# KeypadKeyboard.net
KiCad netlist of a schematic drawn in Altium Designer
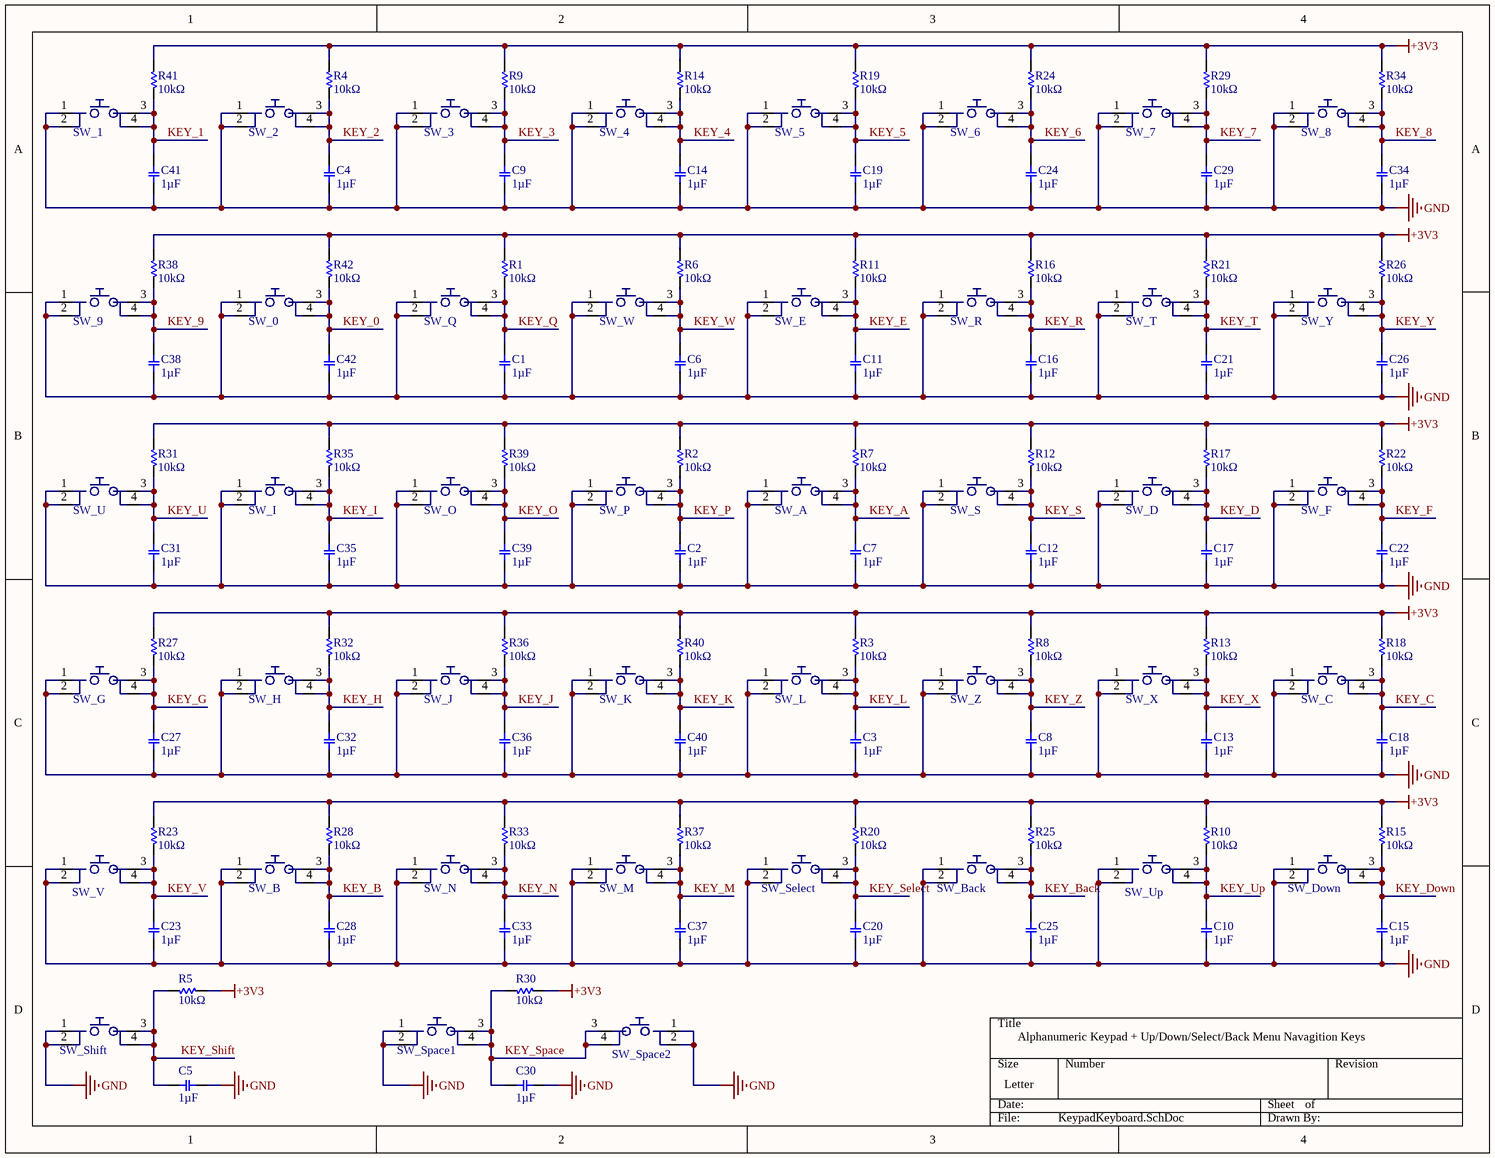
[diagram p0: KeypadKeyboard.SchDoc]

(export (version "E")
  (design (tool "Eeschema 10.0.6"))
  (components
    (comp (ref "C1")
      (value "1µF")
      (footprint "C0805(2012)_NP_med")
      (description "SMT Capacitor")
      (fields (field (name "TOLERANCE") "X7R"))
      (libsource (lib "ChipComponents") (part "CPN_SMT"))
    )
    (comp (ref "C2")
      (value "1µF")
      (footprint "C0805(2012)_NP_med")
      (description "SMT Capacitor")
      (fields (field (name "TOLERANCE") "X7R"))
      (libsource (lib "ChipComponents") (part "CPN_SMT"))
    )
    (comp (ref "C3")
      (value "1µF")
      (footprint "C0805(2012)_NP_med")
      (description "SMT Capacitor")
      (fields (field (name "TOLERANCE") "X7R"))
      (libsource (lib "ChipComponents") (part "CPN_SMT"))
    )
    (comp (ref "C4")
      (value "1µF")
      (footprint "C0805(2012)_NP_med")
      (description "SMT Capacitor")
      (fields (field (name "TOLERANCE") "X7R"))
      (libsource (lib "ChipComponents") (part "CPN_SMT"))
    )
    (comp (ref "C5")
      (value "1µF")
      (footprint "C0805(2012)_NP_med")
      (description "SMT Capacitor")
      (fields (field (name "TOLERANCE") "X7R"))
      (libsource (lib "ChipComponents") (part "CPN_SMT"))
    )
    (comp (ref "C6")
      (value "1µF")
      (footprint "C0805(2012)_NP_med")
      (description "SMT Capacitor")
      (fields (field (name "TOLERANCE") "X7R"))
      (libsource (lib "ChipComponents") (part "CPN_SMT"))
    )
    (comp (ref "C7")
      (value "1µF")
      (footprint "C0805(2012)_NP_med")
      (description "SMT Capacitor")
      (fields (field (name "TOLERANCE") "X7R"))
      (libsource (lib "ChipComponents") (part "CPN_SMT"))
    )
    (comp (ref "C8")
      (value "1µF")
      (footprint "C0805(2012)_NP_med")
      (description "SMT Capacitor")
      (fields (field (name "TOLERANCE") "X7R"))
      (libsource (lib "ChipComponents") (part "CPN_SMT"))
    )
    (comp (ref "C9")
      (value "1µF")
      (footprint "C0805(2012)_NP_med")
      (description "SMT Capacitor")
      (fields (field (name "TOLERANCE") "X7R"))
      (libsource (lib "ChipComponents") (part "CPN_SMT"))
    )
    (comp (ref "C10")
      (value "1µF")
      (footprint "C0805(2012)_NP_med")
      (description "SMT Capacitor")
      (fields (field (name "TOLERANCE") "X7R"))
      (libsource (lib "ChipComponents") (part "CPN_SMT"))
    )
    (comp (ref "C11")
      (value "1µF")
      (footprint "C0805(2012)_NP_med")
      (description "SMT Capacitor")
      (fields (field (name "TOLERANCE") "X7R"))
      (libsource (lib "ChipComponents") (part "CPN_SMT"))
    )
    (comp (ref "C12")
      (value "1µF")
      (footprint "C0805(2012)_NP_med")
      (description "SMT Capacitor")
      (fields (field (name "TOLERANCE") "X7R"))
      (libsource (lib "ChipComponents") (part "CPN_SMT"))
    )
    (comp (ref "C13")
      (value "1µF")
      (footprint "C0805(2012)_NP_med")
      (description "SMT Capacitor")
      (fields (field (name "TOLERANCE") "X7R"))
      (libsource (lib "ChipComponents") (part "CPN_SMT"))
    )
    (comp (ref "C14")
      (value "1µF")
      (footprint "C0805(2012)_NP_med")
      (description "SMT Capacitor")
      (fields (field (name "TOLERANCE") "X7R"))
      (libsource (lib "ChipComponents") (part "CPN_SMT"))
    )
    (comp (ref "C15")
      (value "1µF")
      (footprint "C0805(2012)_NP_med")
      (description "SMT Capacitor")
      (fields (field (name "TOLERANCE") "X7R"))
      (libsource (lib "ChipComponents") (part "CPN_SMT"))
    )
    (comp (ref "C16")
      (value "1µF")
      (footprint "C0805(2012)_NP_med")
      (description "SMT Capacitor")
      (fields (field (name "TOLERANCE") "X7R"))
      (libsource (lib "ChipComponents") (part "CPN_SMT"))
    )
    (comp (ref "C17")
      (value "1µF")
      (footprint "C0805(2012)_NP_med")
      (description "SMT Capacitor")
      (fields (field (name "TOLERANCE") "X7R"))
      (libsource (lib "ChipComponents") (part "CPN_SMT"))
    )
    (comp (ref "C18")
      (value "1µF")
      (footprint "C0805(2012)_NP_med")
      (description "SMT Capacitor")
      (fields (field (name "TOLERANCE") "X7R"))
      (libsource (lib "ChipComponents") (part "CPN_SMT"))
    )
    (comp (ref "C19")
      (value "1µF")
      (footprint "C0805(2012)_NP_med")
      (description "SMT Capacitor")
      (fields (field (name "TOLERANCE") "X7R"))
      (libsource (lib "ChipComponents") (part "CPN_SMT"))
    )
    (comp (ref "C20")
      (value "1µF")
      (footprint "C0805(2012)_NP_med")
      (description "SMT Capacitor")
      (fields (field (name "TOLERANCE") "X7R"))
      (libsource (lib "ChipComponents") (part "CPN_SMT"))
    )
    (comp (ref "C21")
      (value "1µF")
      (footprint "C0805(2012)_NP_med")
      (description "SMT Capacitor")
      (fields (field (name "TOLERANCE") "X7R"))
      (libsource (lib "ChipComponents") (part "CPN_SMT"))
    )
    (comp (ref "C22")
      (value "1µF")
      (footprint "C0805(2012)_NP_med")
      (description "SMT Capacitor")
      (fields (field (name "TOLERANCE") "X7R"))
      (libsource (lib "ChipComponents") (part "CPN_SMT"))
    )
    (comp (ref "C23")
      (value "1µF")
      (footprint "C0805(2012)_NP_med")
      (description "SMT Capacitor")
      (fields (field (name "TOLERANCE") "X7R"))
      (libsource (lib "ChipComponents") (part "CPN_SMT"))
    )
    (comp (ref "C24")
      (value "1µF")
      (footprint "C0805(2012)_NP_med")
      (description "SMT Capacitor")
      (fields (field (name "TOLERANCE") "X7R"))
      (libsource (lib "ChipComponents") (part "CPN_SMT"))
    )
    (comp (ref "C25")
      (value "1µF")
      (footprint "C0805(2012)_NP_med")
      (description "SMT Capacitor")
      (fields (field (name "TOLERANCE") "X7R"))
      (libsource (lib "ChipComponents") (part "CPN_SMT"))
    )
    (comp (ref "C26")
      (value "1µF")
      (footprint "C0805(2012)_NP_med")
      (description "SMT Capacitor")
      (fields (field (name "TOLERANCE") "X7R"))
      (libsource (lib "ChipComponents") (part "CPN_SMT"))
    )
    (comp (ref "C27")
      (value "1µF")
      (footprint "C0805(2012)_NP_med")
      (description "SMT Capacitor")
      (fields (field (name "TOLERANCE") "X7R"))
      (libsource (lib "ChipComponents") (part "CPN_SMT"))
    )
    (comp (ref "C28")
      (value "1µF")
      (footprint "C0805(2012)_NP_med")
      (description "SMT Capacitor")
      (fields (field (name "TOLERANCE") "X7R"))
      (libsource (lib "ChipComponents") (part "CPN_SMT"))
    )
    (comp (ref "C29")
      (value "1µF")
      (footprint "C0805(2012)_NP_med")
      (description "SMT Capacitor")
      (fields (field (name "TOLERANCE") "X7R"))
      (libsource (lib "ChipComponents") (part "CPN_SMT"))
    )
    (comp (ref "C30")
      (value "1µF")
      (footprint "C0805(2012)_NP_med")
      (description "SMT Capacitor")
      (fields (field (name "TOLERANCE") "X7R"))
      (libsource (lib "ChipComponents") (part "CPN_SMT"))
    )
    (comp (ref "C31")
      (value "1µF")
      (footprint "C0805(2012)_NP_med")
      (description "SMT Capacitor")
      (fields (field (name "TOLERANCE") "X7R"))
      (libsource (lib "ChipComponents") (part "CPN_SMT"))
    )
    (comp (ref "C32")
      (value "1µF")
      (footprint "C0805(2012)_NP_med")
      (description "SMT Capacitor")
      (fields (field (name "TOLERANCE") "X7R"))
      (libsource (lib "ChipComponents") (part "CPN_SMT"))
    )
    (comp (ref "C33")
      (value "1µF")
      (footprint "C0805(2012)_NP_med")
      (description "SMT Capacitor")
      (fields (field (name "TOLERANCE") "X7R"))
      (libsource (lib "ChipComponents") (part "CPN_SMT"))
    )
    (comp (ref "C34")
      (value "1µF")
      (footprint "C0805(2012)_NP_med")
      (description "SMT Capacitor")
      (fields (field (name "TOLERANCE") "X7R"))
      (libsource (lib "ChipComponents") (part "CPN_SMT"))
    )
    (comp (ref "C35")
      (value "1µF")
      (footprint "C0805(2012)_NP_med")
      (description "SMT Capacitor")
      (fields (field (name "TOLERANCE") "X7R"))
      (libsource (lib "ChipComponents") (part "CPN_SMT"))
    )
    (comp (ref "C36")
      (value "1µF")
      (footprint "C0805(2012)_NP_med")
      (description "SMT Capacitor")
      (fields (field (name "TOLERANCE") "X7R"))
      (libsource (lib "ChipComponents") (part "CPN_SMT"))
    )
    (comp (ref "C37")
      (value "1µF")
      (footprint "C0805(2012)_NP_med")
      (description "SMT Capacitor")
      (fields (field (name "TOLERANCE") "X7R"))
      (libsource (lib "ChipComponents") (part "CPN_SMT"))
    )
    (comp (ref "C38")
      (value "1µF")
      (footprint "C0805(2012)_NP_med")
      (description "SMT Capacitor")
      (fields (field (name "TOLERANCE") "X7R"))
      (libsource (lib "ChipComponents") (part "CPN_SMT"))
    )
    (comp (ref "C39")
      (value "1µF")
      (footprint "C0805(2012)_NP_med")
      (description "SMT Capacitor")
      (fields (field (name "TOLERANCE") "X7R"))
      (libsource (lib "ChipComponents") (part "CPN_SMT"))
    )
    (comp (ref "C40")
      (value "1µF")
      (footprint "C0805(2012)_NP_med")
      (description "SMT Capacitor")
      (fields (field (name "TOLERANCE") "X7R"))
      (libsource (lib "ChipComponents") (part "CPN_SMT"))
    )
    (comp (ref "C41")
      (value "1µF")
      (footprint "C0805(2012)_NP_med")
      (description "SMT Capacitor")
      (fields (field (name "TOLERANCE") "X7R"))
      (libsource (lib "ChipComponents") (part "CPN_SMT"))
    )
    (comp (ref "C42")
      (value "1µF")
      (footprint "C0805(2012)_NP_med")
      (description "SMT Capacitor")
      (fields (field (name "TOLERANCE") "X7R"))
      (libsource (lib "ChipComponents") (part "CPN_SMT"))
    )
    (comp (ref "R1")
      (value "10kΩ")
      (footprint "R0805(2012)_med")
      (description "SMT resistor")
      (fields (field (name "TOLERANCE") "1%"))
      (libsource (lib "ChipComponents") (part "RES_SMT"))
    )
    (comp (ref "R2")
      (value "10kΩ")
      (footprint "R0805(2012)_med")
      (description "SMT resistor")
      (fields (field (name "TOLERANCE") "1%"))
      (libsource (lib "ChipComponents") (part "RES_SMT"))
    )
    (comp (ref "R3")
      (value "10kΩ")
      (footprint "R0805(2012)_med")
      (description "SMT resistor")
      (fields (field (name "TOLERANCE") "1%"))
      (libsource (lib "ChipComponents") (part "RES_SMT"))
    )
    (comp (ref "R4")
      (value "10kΩ")
      (footprint "R0805(2012)_med")
      (description "SMT resistor")
      (fields (field (name "TOLERANCE") "1%"))
      (libsource (lib "ChipComponents") (part "RES_SMT"))
    )
    (comp (ref "R5")
      (value "10kΩ")
      (footprint "R0805(2012)_med")
      (description "SMT resistor")
      (fields (field (name "TOLERANCE") "1%"))
      (libsource (lib "ChipComponents") (part "RES_SMT"))
    )
    (comp (ref "R6")
      (value "10kΩ")
      (footprint "R0805(2012)_med")
      (description "SMT resistor")
      (fields (field (name "TOLERANCE") "1%"))
      (libsource (lib "ChipComponents") (part "RES_SMT"))
    )
    (comp (ref "R7")
      (value "10kΩ")
      (footprint "R0805(2012)_med")
      (description "SMT resistor")
      (fields (field (name "TOLERANCE") "1%"))
      (libsource (lib "ChipComponents") (part "RES_SMT"))
    )
    (comp (ref "R8")
      (value "10kΩ")
      (footprint "R0805(2012)_med")
      (description "SMT resistor")
      (fields (field (name "TOLERANCE") "1%"))
      (libsource (lib "ChipComponents") (part "RES_SMT"))
    )
    (comp (ref "R9")
      (value "10kΩ")
      (footprint "R0805(2012)_med")
      (description "SMT resistor")
      (fields (field (name "TOLERANCE") "1%"))
      (libsource (lib "ChipComponents") (part "RES_SMT"))
    )
    (comp (ref "R10")
      (value "10kΩ")
      (footprint "R0805(2012)_med")
      (description "SMT resistor")
      (fields (field (name "TOLERANCE") "1%"))
      (libsource (lib "ChipComponents") (part "RES_SMT"))
    )
    (comp (ref "R11")
      (value "10kΩ")
      (footprint "R0805(2012)_med")
      (description "SMT resistor")
      (fields (field (name "TOLERANCE") "1%"))
      (libsource (lib "ChipComponents") (part "RES_SMT"))
    )
    (comp (ref "R12")
      (value "10kΩ")
      (footprint "R0805(2012)_med")
      (description "SMT resistor")
      (fields (field (name "TOLERANCE") "1%"))
      (libsource (lib "ChipComponents") (part "RES_SMT"))
    )
    (comp (ref "R13")
      (value "10kΩ")
      (footprint "R0805(2012)_med")
      (description "SMT resistor")
      (fields (field (name "TOLERANCE") "1%"))
      (libsource (lib "ChipComponents") (part "RES_SMT"))
    )
    (comp (ref "R14")
      (value "10kΩ")
      (footprint "R0805(2012)_med")
      (description "SMT resistor")
      (fields (field (name "TOLERANCE") "1%"))
      (libsource (lib "ChipComponents") (part "RES_SMT"))
    )
    (comp (ref "R15")
      (value "10kΩ")
      (footprint "R0805(2012)_med")
      (description "SMT resistor")
      (fields (field (name "TOLERANCE") "1%"))
      (libsource (lib "ChipComponents") (part "RES_SMT"))
    )
    (comp (ref "R16")
      (value "10kΩ")
      (footprint "R0805(2012)_med")
      (description "SMT resistor")
      (fields (field (name "TOLERANCE") "1%"))
      (libsource (lib "ChipComponents") (part "RES_SMT"))
    )
    (comp (ref "R17")
      (value "10kΩ")
      (footprint "R0805(2012)_med")
      (description "SMT resistor")
      (fields (field (name "TOLERANCE") "1%"))
      (libsource (lib "ChipComponents") (part "RES_SMT"))
    )
    (comp (ref "R18")
      (value "10kΩ")
      (footprint "R0805(2012)_med")
      (description "SMT resistor")
      (fields (field (name "TOLERANCE") "1%"))
      (libsource (lib "ChipComponents") (part "RES_SMT"))
    )
    (comp (ref "R19")
      (value "10kΩ")
      (footprint "R0805(2012)_med")
      (description "SMT resistor")
      (fields (field (name "TOLERANCE") "1%"))
      (libsource (lib "ChipComponents") (part "RES_SMT"))
    )
    (comp (ref "R20")
      (value "10kΩ")
      (footprint "R0805(2012)_med")
      (description "SMT resistor")
      (fields (field (name "TOLERANCE") "1%"))
      (libsource (lib "ChipComponents") (part "RES_SMT"))
    )
    (comp (ref "R21")
      (value "10kΩ")
      (footprint "R0805(2012)_med")
      (description "SMT resistor")
      (fields (field (name "TOLERANCE") "1%"))
      (libsource (lib "ChipComponents") (part "RES_SMT"))
    )
    (comp (ref "R22")
      (value "10kΩ")
      (footprint "R0805(2012)_med")
      (description "SMT resistor")
      (fields (field (name "TOLERANCE") "1%"))
      (libsource (lib "ChipComponents") (part "RES_SMT"))
    )
    (comp (ref "R23")
      (value "10kΩ")
      (footprint "R0805(2012)_med")
      (description "SMT resistor")
      (fields (field (name "TOLERANCE") "1%"))
      (libsource (lib "ChipComponents") (part "RES_SMT"))
    )
    (comp (ref "R24")
      (value "10kΩ")
      (footprint "R0805(2012)_med")
      (description "SMT resistor")
      (fields (field (name "TOLERANCE") "1%"))
      (libsource (lib "ChipComponents") (part "RES_SMT"))
    )
    (comp (ref "R25")
      (value "10kΩ")
      (footprint "R0805(2012)_med")
      (description "SMT resistor")
      (fields (field (name "TOLERANCE") "1%"))
      (libsource (lib "ChipComponents") (part "RES_SMT"))
    )
    (comp (ref "R26")
      (value "10kΩ")
      (footprint "R0805(2012)_med")
      (description "SMT resistor")
      (fields (field (name "TOLERANCE") "1%"))
      (libsource (lib "ChipComponents") (part "RES_SMT"))
    )
    (comp (ref "R27")
      (value "10kΩ")
      (footprint "R0805(2012)_med")
      (description "SMT resistor")
      (fields (field (name "TOLERANCE") "1%"))
      (libsource (lib "ChipComponents") (part "RES_SMT"))
    )
    (comp (ref "R28")
      (value "10kΩ")
      (footprint "R0805(2012)_med")
      (description "SMT resistor")
      (fields (field (name "TOLERANCE") "1%"))
      (libsource (lib "ChipComponents") (part "RES_SMT"))
    )
    (comp (ref "R29")
      (value "10kΩ")
      (footprint "R0805(2012)_med")
      (description "SMT resistor")
      (fields (field (name "TOLERANCE") "1%"))
      (libsource (lib "ChipComponents") (part "RES_SMT"))
    )
    (comp (ref "R30")
      (value "10kΩ")
      (footprint "R0805(2012)_med")
      (description "SMT resistor")
      (fields (field (name "TOLERANCE") "1%"))
      (libsource (lib "ChipComponents") (part "RES_SMT"))
    )
    (comp (ref "R31")
      (value "10kΩ")
      (footprint "R0805(2012)_med")
      (description "SMT resistor")
      (fields (field (name "TOLERANCE") "1%"))
      (libsource (lib "ChipComponents") (part "RES_SMT"))
    )
    (comp (ref "R32")
      (value "10kΩ")
      (footprint "R0805(2012)_med")
      (description "SMT resistor")
      (fields (field (name "TOLERANCE") "1%"))
      (libsource (lib "ChipComponents") (part "RES_SMT"))
    )
    (comp (ref "R33")
      (value "10kΩ")
      (footprint "R0805(2012)_med")
      (description "SMT resistor")
      (fields (field (name "TOLERANCE") "1%"))
      (libsource (lib "ChipComponents") (part "RES_SMT"))
    )
    (comp (ref "R34")
      (value "10kΩ")
      (footprint "R0805(2012)_med")
      (description "SMT resistor")
      (fields (field (name "TOLERANCE") "1%"))
      (libsource (lib "ChipComponents") (part "RES_SMT"))
    )
    (comp (ref "R35")
      (value "10kΩ")
      (footprint "R0805(2012)_med")
      (description "SMT resistor")
      (fields (field (name "TOLERANCE") "1%"))
      (libsource (lib "ChipComponents") (part "RES_SMT"))
    )
    (comp (ref "R36")
      (value "10kΩ")
      (footprint "R0805(2012)_med")
      (description "SMT resistor")
      (fields (field (name "TOLERANCE") "1%"))
      (libsource (lib "ChipComponents") (part "RES_SMT"))
    )
    (comp (ref "R37")
      (value "10kΩ")
      (footprint "R0805(2012)_med")
      (description "SMT resistor")
      (fields (field (name "TOLERANCE") "1%"))
      (libsource (lib "ChipComponents") (part "RES_SMT"))
    )
    (comp (ref "R38")
      (value "10kΩ")
      (footprint "R0805(2012)_med")
      (description "SMT resistor")
      (fields (field (name "TOLERANCE") "1%"))
      (libsource (lib "ChipComponents") (part "RES_SMT"))
    )
    (comp (ref "R39")
      (value "10kΩ")
      (footprint "R0805(2012)_med")
      (description "SMT resistor")
      (fields (field (name "TOLERANCE") "1%"))
      (libsource (lib "ChipComponents") (part "RES_SMT"))
    )
    (comp (ref "R40")
      (value "10kΩ")
      (footprint "R0805(2012)_med")
      (description "SMT resistor")
      (fields (field (name "TOLERANCE") "1%"))
      (libsource (lib "ChipComponents") (part "RES_SMT"))
    )
    (comp (ref "R41")
      (value "10kΩ")
      (footprint "R0805(2012)_med")
      (description "SMT resistor")
      (fields (field (name "TOLERANCE") "1%"))
      (libsource (lib "ChipComponents") (part "RES_SMT"))
    )
    (comp (ref "R42")
      (value "10kΩ")
      (footprint "R0805(2012)_med")
      (description "SMT resistor")
      (fields (field (name "TOLERANCE") "1%"))
      (libsource (lib "ChipComponents") (part "RES_SMT"))
    )
    (comp (ref "SW_0")
      (value "TE 1825910-6")
      (footprint "TE 1825910-6")
      (description "SWITCH TACTILE SPST-NO 0.05A 24V")
      (fields
        (field (name "MANUFACTURER") "TE Connectivity Alcoswitch Switches")
        (field (name "MANUFACTURER PART NUMBER") "1825910-6")
      )
      (libsource (lib "RFIDSchematicLibrary") (part "TE 1825910-6"))
    )
    (comp (ref "SW_1")
      (value "1825910-6")
      (footprint "TE 1825910-6")
      (description "SWITCH TACTILE SPST-NO 0.05A 24V")
      (fields (field (name "MANUFACTURER") "TE Connectivity Alcoswitch Switches"))
      (libsource (lib "RFIDSchematicLibrary") (part "1825910-6"))
    )
    (comp (ref "SW_2")
      (value "1825910-6")
      (footprint "TE 1825910-6")
      (description "SWITCH TACTILE SPST-NO 0.05A 24V")
      (fields (field (name "MANUFACTURER") "TE Connectivity Alcoswitch Switches"))
      (libsource (lib "RFIDSchematicLibrary") (part "1825910-6"))
    )
    (comp (ref "SW_3")
      (value "1825910-6")
      (footprint "TE 1825910-6")
      (description "SWITCH TACTILE SPST-NO 0.05A 24V")
      (fields (field (name "MANUFACTURER") "TE Connectivity Alcoswitch Switches"))
      (libsource (lib "RFIDSchematicLibrary") (part "1825910-6"))
    )
    (comp (ref "SW_4")
      (value "1825910-6")
      (footprint "TE 1825910-6")
      (description "SWITCH TACTILE SPST-NO 0.05A 24V")
      (fields (field (name "MANUFACTURER") "TE Connectivity Alcoswitch Switches"))
      (libsource (lib "RFIDSchematicLibrary") (part "1825910-6"))
    )
    (comp (ref "SW_5")
      (value "1825910-6")
      (footprint "TE 1825910-6")
      (description "SWITCH TACTILE SPST-NO 0.05A 24V")
      (fields (field (name "MANUFACTURER") "TE Connectivity Alcoswitch Switches"))
      (libsource (lib "RFIDSchematicLibrary") (part "1825910-6"))
    )
    (comp (ref "SW_6")
      (value "1825910-6")
      (footprint "TE 1825910-6")
      (description "SWITCH TACTILE SPST-NO 0.05A 24V")
      (fields (field (name "MANUFACTURER") "TE Connectivity Alcoswitch Switches"))
      (libsource (lib "RFIDSchematicLibrary") (part "1825910-6"))
    )
    (comp (ref "SW_7")
      (value "1825910-6")
      (footprint "TE 1825910-6")
      (description "SWITCH TACTILE SPST-NO 0.05A 24V")
      (fields (field (name "MANUFACTURER") "TE Connectivity Alcoswitch Switches"))
      (libsource (lib "RFIDSchematicLibrary") (part "1825910-6"))
    )
    (comp (ref "SW_8")
      (value "1825910-6")
      (footprint "TE 1825910-6")
      (description "SWITCH TACTILE SPST-NO 0.05A 24V")
      (fields (field (name "MANUFACTURER") "TE Connectivity Alcoswitch Switches"))
      (libsource (lib "RFIDSchematicLibrary") (part "1825910-6"))
    )
    (comp (ref "SW_9")
      (value "1825910-6")
      (footprint "TE 1825910-6")
      (description "SWITCH TACTILE SPST-NO 0.05A 24V")
      (fields (field (name "MANUFACTURER") "TE Connectivity Alcoswitch Switches"))
      (libsource (lib "RFIDSchematicLibrary") (part "1825910-6"))
    )
    (comp (ref "SW_A")
      (value "1825910-6")
      (footprint "TE 1825910-6")
      (description "SWITCH TACTILE SPST-NO 0.05A 24V")
      (fields (field (name "MANUFACTURER") "TE Connectivity Alcoswitch Switches"))
      (libsource (lib "RFIDSchematicLibrary") (part "1825910-6"))
    )
    (comp (ref "SW_B")
      (value "1825910-6")
      (footprint "TE 1825910-6")
      (description "SWITCH TACTILE SPST-NO 0.05A 24V")
      (fields (field (name "MANUFACTURER") "TE Connectivity Alcoswitch Switches"))
      (libsource (lib "RFIDSchematicLibrary") (part "1825910-6"))
    )
    (comp (ref "SW_Back")
      (value "1825910-6")
      (footprint "TE 1825910-6")
      (description "SWITCH TACTILE SPST-NO 0.05A 24V")
      (fields (field (name "MANUFACTURER") "TE Connectivity Alcoswitch Switches"))
      (libsource (lib "RFIDSchematicLibrary") (part "1825910-6"))
    )
    (comp (ref "SW_C")
      (value "1825910-6")
      (footprint "TE 1825910-6")
      (description "SWITCH TACTILE SPST-NO 0.05A 24V")
      (fields (field (name "MANUFACTURER") "TE Connectivity Alcoswitch Switches"))
      (libsource (lib "RFIDSchematicLibrary") (part "1825910-6"))
    )
    (comp (ref "SW_D")
      (value "1825910-6")
      (footprint "TE 1825910-6")
      (description "SWITCH TACTILE SPST-NO 0.05A 24V")
      (fields (field (name "MANUFACTURER") "TE Connectivity Alcoswitch Switches"))
      (libsource (lib "RFIDSchematicLibrary") (part "1825910-6"))
    )
    (comp (ref "SW_Down")
      (value "1825910-6")
      (footprint "TE 1825910-6")
      (description "SWITCH TACTILE SPST-NO 0.05A 24V")
      (fields (field (name "MANUFACTURER") "TE Connectivity Alcoswitch Switches"))
      (libsource (lib "RFIDSchematicLibrary") (part "1825910-6"))
    )
    (comp (ref "SW_E")
      (value "1825910-6")
      (footprint "TE 1825910-6")
      (description "SWITCH TACTILE SPST-NO 0.05A 24V")
      (fields (field (name "MANUFACTURER") "TE Connectivity Alcoswitch Switches"))
      (libsource (lib "RFIDSchematicLibrary") (part "1825910-6"))
    )
    (comp (ref "SW_F")
      (value "1825910-6")
      (footprint "TE 1825910-6")
      (description "SWITCH TACTILE SPST-NO 0.05A 24V")
      (fields (field (name "MANUFACTURER") "TE Connectivity Alcoswitch Switches"))
      (libsource (lib "RFIDSchematicLibrary") (part "1825910-6"))
    )
    (comp (ref "SW_G")
      (value "1825910-6")
      (footprint "TE 1825910-6")
      (description "SWITCH TACTILE SPST-NO 0.05A 24V")
      (fields (field (name "MANUFACTURER") "TE Connectivity Alcoswitch Switches"))
      (libsource (lib "RFIDSchematicLibrary") (part "1825910-6"))
    )
    (comp (ref "SW_H")
      (value "1825910-6")
      (footprint "TE 1825910-6")
      (description "SWITCH TACTILE SPST-NO 0.05A 24V")
      (fields (field (name "MANUFACTURER") "TE Connectivity Alcoswitch Switches"))
      (libsource (lib "RFIDSchematicLibrary") (part "1825910-6"))
    )
    (comp (ref "SW_I")
      (value "1825910-6")
      (footprint "TE 1825910-6")
      (description "SWITCH TACTILE SPST-NO 0.05A 24V")
      (fields (field (name "MANUFACTURER") "TE Connectivity Alcoswitch Switches"))
      (libsource (lib "RFIDSchematicLibrary") (part "1825910-6"))
    )
    (comp (ref "SW_J")
      (value "1825910-6")
      (footprint "TE 1825910-6")
      (description "SWITCH TACTILE SPST-NO 0.05A 24V")
      (fields (field (name "MANUFACTURER") "TE Connectivity Alcoswitch Switches"))
      (libsource (lib "RFIDSchematicLibrary") (part "1825910-6"))
    )
    (comp (ref "SW_K")
      (value "1825910-6")
      (footprint "TE 1825910-6")
      (description "SWITCH TACTILE SPST-NO 0.05A 24V")
      (fields (field (name "MANUFACTURER") "TE Connectivity Alcoswitch Switches"))
      (libsource (lib "RFIDSchematicLibrary") (part "1825910-6"))
    )
    (comp (ref "SW_L")
      (value "1825910-6")
      (footprint "TE 1825910-6")
      (description "SWITCH TACTILE SPST-NO 0.05A 24V")
      (fields (field (name "MANUFACTURER") "TE Connectivity Alcoswitch Switches"))
      (libsource (lib "RFIDSchematicLibrary") (part "1825910-6"))
    )
    (comp (ref "SW_M")
      (value "1825910-6")
      (footprint "TE 1825910-6")
      (description "SWITCH TACTILE SPST-NO 0.05A 24V")
      (fields (field (name "MANUFACTURER") "TE Connectivity Alcoswitch Switches"))
      (libsource (lib "RFIDSchematicLibrary") (part "1825910-6"))
    )
    (comp (ref "SW_N")
      (value "1825910-6")
      (footprint "TE 1825910-6")
      (description "SWITCH TACTILE SPST-NO 0.05A 24V")
      (fields (field (name "MANUFACTURER") "TE Connectivity Alcoswitch Switches"))
      (libsource (lib "RFIDSchematicLibrary") (part "1825910-6"))
    )
    (comp (ref "SW_O")
      (value "1825910-6")
      (footprint "TE 1825910-6")
      (description "SWITCH TACTILE SPST-NO 0.05A 24V")
      (fields (field (name "MANUFACTURER") "TE Connectivity Alcoswitch Switches"))
      (libsource (lib "RFIDSchematicLibrary") (part "1825910-6"))
    )
    (comp (ref "SW_P")
      (value "1825910-6")
      (footprint "TE 1825910-6")
      (description "SWITCH TACTILE SPST-NO 0.05A 24V")
      (fields (field (name "MANUFACTURER") "TE Connectivity Alcoswitch Switches"))
      (libsource (lib "RFIDSchematicLibrary") (part "1825910-6"))
    )
    (comp (ref "SW_Q")
      (value "1825910-6")
      (footprint "TE 1825910-6")
      (description "SWITCH TACTILE SPST-NO 0.05A 24V")
      (fields (field (name "MANUFACTURER") "TE Connectivity Alcoswitch Switches"))
      (libsource (lib "RFIDSchematicLibrary") (part "1825910-6"))
    )
    (comp (ref "SW_R")
      (value "1825910-6")
      (footprint "TE 1825910-6")
      (description "SWITCH TACTILE SPST-NO 0.05A 24V")
      (fields (field (name "MANUFACTURER") "TE Connectivity Alcoswitch Switches"))
      (libsource (lib "RFIDSchematicLibrary") (part "1825910-6"))
    )
    (comp (ref "SW_S")
      (value "1825910-6")
      (footprint "TE 1825910-6")
      (description "SWITCH TACTILE SPST-NO 0.05A 24V")
      (fields (field (name "MANUFACTURER") "TE Connectivity Alcoswitch Switches"))
      (libsource (lib "RFIDSchematicLibrary") (part "1825910-6"))
    )
    (comp (ref "SW_Select")
      (value "1825910-6")
      (footprint "TE 1825910-6")
      (description "SWITCH TACTILE SPST-NO 0.05A 24V")
      (fields (field (name "MANUFACTURER") "TE Connectivity Alcoswitch Switches"))
      (libsource (lib "RFIDSchematicLibrary") (part "1825910-6"))
    )
    (comp (ref "SW_Shift")
      (value "1825910-6")
      (footprint "TE 1825910-6")
      (description "SWITCH TACTILE SPST-NO 0.05A 24V")
      (fields (field (name "MANUFACTURER") "TE Connectivity Alcoswitch Switches"))
      (libsource (lib "RFIDSchematicLibrary") (part "1825910-6"))
    )
    (comp (ref "SW_Space1")
      (value "1825910-6")
      (footprint "TE 1825910-6")
      (description "SWITCH TACTILE SPST-NO 0.05A 24V")
      (fields (field (name "MANUFACTURER") "TE Connectivity Alcoswitch Switches"))
      (libsource (lib "RFIDSchematicLibrary") (part "1825910-6"))
    )
    (comp (ref "SW_Space2")
      (value "1825910-6")
      (footprint "TE 1825910-6")
      (description "SWITCH TACTILE SPST-NO 0.05A 24V")
      (fields (field (name "MANUFACTURER") "TE Connectivity Alcoswitch Switches"))
      (libsource (lib "RFIDSchematicLibrary") (part "1825910-6"))
    )
    (comp (ref "SW_T")
      (value "1825910-6")
      (footprint "TE 1825910-6")
      (description "SWITCH TACTILE SPST-NO 0.05A 24V")
      (fields (field (name "MANUFACTURER") "TE Connectivity Alcoswitch Switches"))
      (libsource (lib "RFIDSchematicLibrary") (part "1825910-6"))
    )
    (comp (ref "SW_U")
      (value "1825910-6")
      (footprint "TE 1825910-6")
      (description "SWITCH TACTILE SPST-NO 0.05A 24V")
      (fields (field (name "MANUFACTURER") "TE Connectivity Alcoswitch Switches"))
      (libsource (lib "RFIDSchematicLibrary") (part "1825910-6"))
    )
    (comp (ref "SW_Up")
      (value "1825910-6")
      (footprint "TE 1825910-6")
      (description "SWITCH TACTILE SPST-NO 0.05A 24V")
      (fields (field (name "MANUFACTURER") "TE Connectivity Alcoswitch Switches"))
      (libsource (lib "RFIDSchematicLibrary") (part "1825910-6"))
    )
    (comp (ref "SW_V")
      (value "1825910-6")
      (footprint "TE 1825910-6")
      (description "SWITCH TACTILE SPST-NO 0.05A 24V")
      (fields (field (name "MANUFACTURER") "TE Connectivity Alcoswitch Switches"))
      (libsource (lib "RFIDSchematicLibrary") (part "1825910-6"))
    )
    (comp (ref "SW_W")
      (value "1825910-6")
      (footprint "TE 1825910-6")
      (description "SWITCH TACTILE SPST-NO 0.05A 24V")
      (fields (field (name "MANUFACTURER") "TE Connectivity Alcoswitch Switches"))
      (libsource (lib "RFIDSchematicLibrary") (part "1825910-6"))
    )
    (comp (ref "SW_X")
      (value "1825910-6")
      (footprint "TE 1825910-6")
      (description "SWITCH TACTILE SPST-NO 0.05A 24V")
      (fields (field (name "MANUFACTURER") "TE Connectivity Alcoswitch Switches"))
      (libsource (lib "RFIDSchematicLibrary") (part "1825910-6"))
    )
    (comp (ref "SW_Y")
      (value "1825910-6")
      (footprint "TE 1825910-6")
      (description "SWITCH TACTILE SPST-NO 0.05A 24V")
      (fields (field (name "MANUFACTURER") "TE Connectivity Alcoswitch Switches"))
      (libsource (lib "RFIDSchematicLibrary") (part "1825910-6"))
    )
    (comp (ref "SW_Z")
      (value "1825910-6")
      (footprint "TE 1825910-6")
      (description "SWITCH TACTILE SPST-NO 0.05A 24V")
      (fields (field (name "MANUFACTURER") "TE Connectivity Alcoswitch Switches"))
      (libsource (lib "RFIDSchematicLibrary") (part "1825910-6"))
    )
  )
  (nets
    (net (code "1") (name "+3V3") (class "Default")
      (node (ref "R1") (pin "1") (pinfunction "1_1") (pintype "passive"))
      (node (ref "R10") (pin "1") (pinfunction "1_1") (pintype "passive"))
      (node (ref "R11") (pin "1") (pinfunction "1_1") (pintype "passive"))
      (node (ref "R12") (pin "1") (pinfunction "1_1") (pintype "passive"))
      (node (ref "R13") (pin "1") (pinfunction "1_1") (pintype "passive"))
      (node (ref "R14") (pin "1") (pinfunction "1_1") (pintype "passive"))
      (node (ref "R15") (pin "1") (pinfunction "1_1") (pintype "passive"))
      (node (ref "R16") (pin "1") (pinfunction "1_1") (pintype "passive"))
      (node (ref "R17") (pin "1") (pinfunction "1_1") (pintype "passive"))
      (node (ref "R18") (pin "1") (pinfunction "1_1") (pintype "passive"))
      (node (ref "R19") (pin "1") (pinfunction "1_1") (pintype "passive"))
      (node (ref "R2") (pin "1") (pinfunction "1_1") (pintype "passive"))
      (node (ref "R20") (pin "1") (pinfunction "1_1") (pintype "passive"))
      (node (ref "R21") (pin "1") (pinfunction "1_1") (pintype "passive"))
      (node (ref "R22") (pin "1") (pinfunction "1_1") (pintype "passive"))
      (node (ref "R23") (pin "1") (pinfunction "1_1") (pintype "passive"))
      (node (ref "R24") (pin "1") (pinfunction "1_1") (pintype "passive"))
      (node (ref "R25") (pin "1") (pinfunction "1_1") (pintype "passive"))
      (node (ref "R26") (pin "1") (pinfunction "1_1") (pintype "passive"))
      (node (ref "R27") (pin "1") (pinfunction "1_1") (pintype "passive"))
      (node (ref "R28") (pin "1") (pinfunction "1_1") (pintype "passive"))
      (node (ref "R29") (pin "1") (pinfunction "1_1") (pintype "passive"))
      (node (ref "R3") (pin "1") (pinfunction "1_1") (pintype "passive"))
      (node (ref "R30") (pin "1") (pinfunction "1_1") (pintype "passive"))
      (node (ref "R31") (pin "1") (pinfunction "1_1") (pintype "passive"))
      (node (ref "R32") (pin "1") (pinfunction "1_1") (pintype "passive"))
      (node (ref "R33") (pin "1") (pinfunction "1_1") (pintype "passive"))
      (node (ref "R34") (pin "1") (pinfunction "1_1") (pintype "passive"))
      (node (ref "R35") (pin "1") (pinfunction "1_1") (pintype "passive"))
      (node (ref "R36") (pin "1") (pinfunction "1_1") (pintype "passive"))
      (node (ref "R37") (pin "1") (pinfunction "1_1") (pintype "passive"))
      (node (ref "R38") (pin "1") (pinfunction "1_1") (pintype "passive"))
      (node (ref "R39") (pin "1") (pinfunction "1_1") (pintype "passive"))
      (node (ref "R4") (pin "1") (pinfunction "1_1") (pintype "passive"))
      (node (ref "R40") (pin "1") (pinfunction "1_1") (pintype "passive"))
      (node (ref "R41") (pin "1") (pinfunction "1_1") (pintype "passive"))
      (node (ref "R42") (pin "1") (pinfunction "1_1") (pintype "passive"))
      (node (ref "R5") (pin "2") (pinfunction "2_2") (pintype "passive"))
      (node (ref "R6") (pin "1") (pinfunction "1_1") (pintype "passive"))
      (node (ref "R7") (pin "1") (pinfunction "1_1") (pintype "passive"))
      (node (ref "R8") (pin "1") (pinfunction "1_1") (pintype "passive"))
      (node (ref "R9") (pin "1") (pinfunction "1_1") (pintype "passive"))
    )
    (net (code "2") (name "/KEY_0") (class "Default")
      (node (ref "C42") (pin "2") (pinfunction "2_2") (pintype "passive"))
      (node (ref "R42") (pin "2") (pinfunction "2_2") (pintype "passive"))
      (node (ref "SW_0") (pin "3") (pinfunction "3_3") (pintype "passive"))
      (node (ref "SW_0") (pin "4") (pinfunction "4_4") (pintype "passive"))
    )
    (net (code "3") (name "/KEY_1") (class "Default")
      (node (ref "C41") (pin "2") (pinfunction "2_2") (pintype "passive"))
      (node (ref "R41") (pin "2") (pinfunction "2_2") (pintype "passive"))
      (node (ref "SW_1") (pin "3") (pinfunction "3_3") (pintype "passive"))
      (node (ref "SW_1") (pin "4") (pinfunction "4_4") (pintype "passive"))
    )
    (net (code "4") (name "/KEY_2") (class "Default")
      (node (ref "C4") (pin "2") (pinfunction "2_2") (pintype "passive"))
      (node (ref "R4") (pin "2") (pinfunction "2_2") (pintype "passive"))
      (node (ref "SW_2") (pin "3") (pinfunction "3_3") (pintype "passive"))
      (node (ref "SW_2") (pin "4") (pinfunction "4_4") (pintype "passive"))
    )
    (net (code "5") (name "/KEY_3") (class "Default")
      (node (ref "C9") (pin "2") (pinfunction "2_2") (pintype "passive"))
      (node (ref "R9") (pin "2") (pinfunction "2_2") (pintype "passive"))
      (node (ref "SW_3") (pin "3") (pinfunction "3_3") (pintype "passive"))
      (node (ref "SW_3") (pin "4") (pinfunction "4_4") (pintype "passive"))
    )
    (net (code "6") (name "/KEY_4") (class "Default")
      (node (ref "C14") (pin "2") (pinfunction "2_2") (pintype "passive"))
      (node (ref "R14") (pin "2") (pinfunction "2_2") (pintype "passive"))
      (node (ref "SW_4") (pin "3") (pinfunction "3_3") (pintype "passive"))
      (node (ref "SW_4") (pin "4") (pinfunction "4_4") (pintype "passive"))
    )
    (net (code "7") (name "/KEY_5") (class "Default")
      (node (ref "C19") (pin "2") (pinfunction "2_2") (pintype "passive"))
      (node (ref "R19") (pin "2") (pinfunction "2_2") (pintype "passive"))
      (node (ref "SW_5") (pin "3") (pinfunction "3_3") (pintype "passive"))
      (node (ref "SW_5") (pin "4") (pinfunction "4_4") (pintype "passive"))
    )
    (net (code "8") (name "/KEY_6") (class "Default")
      (node (ref "C24") (pin "2") (pinfunction "2_2") (pintype "passive"))
      (node (ref "R24") (pin "2") (pinfunction "2_2") (pintype "passive"))
      (node (ref "SW_6") (pin "3") (pinfunction "3_3") (pintype "passive"))
      (node (ref "SW_6") (pin "4") (pinfunction "4_4") (pintype "passive"))
    )
    (net (code "9") (name "/KEY_7") (class "Default")
      (node (ref "C29") (pin "2") (pinfunction "2_2") (pintype "passive"))
      (node (ref "R29") (pin "2") (pinfunction "2_2") (pintype "passive"))
      (node (ref "SW_7") (pin "3") (pinfunction "3_3") (pintype "passive"))
      (node (ref "SW_7") (pin "4") (pinfunction "4_4") (pintype "passive"))
    )
    (net (code "10") (name "/KEY_8") (class "Default")
      (node (ref "C34") (pin "2") (pinfunction "2_2") (pintype "passive"))
      (node (ref "R34") (pin "2") (pinfunction "2_2") (pintype "passive"))
      (node (ref "SW_8") (pin "3") (pinfunction "3_3") (pintype "passive"))
      (node (ref "SW_8") (pin "4") (pinfunction "4_4") (pintype "passive"))
    )
    (net (code "11") (name "/KEY_9") (class "Default")
      (node (ref "C38") (pin "2") (pinfunction "2_2") (pintype "passive"))
      (node (ref "R38") (pin "2") (pinfunction "2_2") (pintype "passive"))
      (node (ref "SW_9") (pin "3") (pinfunction "3_3") (pintype "passive"))
      (node (ref "SW_9") (pin "4") (pinfunction "4_4") (pintype "passive"))
    )
    (net (code "12") (name "/KEY_A") (class "Default")
      (node (ref "C7") (pin "2") (pinfunction "2_2") (pintype "passive"))
      (node (ref "R7") (pin "2") (pinfunction "2_2") (pintype "passive"))
      (node (ref "SW_A") (pin "3") (pinfunction "3_3") (pintype "passive"))
      (node (ref "SW_A") (pin "4") (pinfunction "4_4") (pintype "passive"))
    )
    (net (code "13") (name "/KEY_B") (class "Default")
      (node (ref "C28") (pin "2") (pinfunction "2_2") (pintype "passive"))
      (node (ref "R28") (pin "2") (pinfunction "2_2") (pintype "passive"))
      (node (ref "SW_B") (pin "3") (pinfunction "3_3") (pintype "passive"))
      (node (ref "SW_B") (pin "4") (pinfunction "4_4") (pintype "passive"))
    )
    (net (code "14") (name "/KEY_Back") (class "Default")
      (node (ref "C25") (pin "2") (pinfunction "2_2") (pintype "passive"))
      (node (ref "R25") (pin "2") (pinfunction "2_2") (pintype "passive"))
      (node (ref "SW_Back") (pin "3") (pinfunction "3_3") (pintype "passive"))
      (node (ref "SW_Back") (pin "4") (pinfunction "4_4") (pintype "passive"))
    )
    (net (code "15") (name "/KEY_C") (class "Default")
      (node (ref "C18") (pin "2") (pinfunction "2_2") (pintype "passive"))
      (node (ref "R18") (pin "2") (pinfunction "2_2") (pintype "passive"))
      (node (ref "SW_C") (pin "3") (pinfunction "3_3") (pintype "passive"))
      (node (ref "SW_C") (pin "4") (pinfunction "4_4") (pintype "passive"))
    )
    (net (code "16") (name "/KEY_D") (class "Default")
      (node (ref "C17") (pin "2") (pinfunction "2_2") (pintype "passive"))
      (node (ref "R17") (pin "2") (pinfunction "2_2") (pintype "passive"))
      (node (ref "SW_D") (pin "3") (pinfunction "3_3") (pintype "passive"))
      (node (ref "SW_D") (pin "4") (pinfunction "4_4") (pintype "passive"))
    )
    (net (code "17") (name "/KEY_Down") (class "Default")
      (node (ref "C15") (pin "2") (pinfunction "2_2") (pintype "passive"))
      (node (ref "R15") (pin "2") (pinfunction "2_2") (pintype "passive"))
      (node (ref "SW_Down") (pin "3") (pinfunction "3_3") (pintype "passive"))
      (node (ref "SW_Down") (pin "4") (pinfunction "4_4") (pintype "passive"))
    )
    (net (code "18") (name "/KEY_E") (class "Default")
      (node (ref "C11") (pin "2") (pinfunction "2_2") (pintype "passive"))
      (node (ref "R11") (pin "2") (pinfunction "2_2") (pintype "passive"))
      (node (ref "SW_E") (pin "3") (pinfunction "3_3") (pintype "passive"))
      (node (ref "SW_E") (pin "4") (pinfunction "4_4") (pintype "passive"))
    )
    (net (code "19") (name "/KEY_F") (class "Default")
      (node (ref "C22") (pin "2") (pinfunction "2_2") (pintype "passive"))
      (node (ref "R22") (pin "2") (pinfunction "2_2") (pintype "passive"))
      (node (ref "SW_F") (pin "3") (pinfunction "3_3") (pintype "passive"))
      (node (ref "SW_F") (pin "4") (pinfunction "4_4") (pintype "passive"))
    )
    (net (code "20") (name "/KEY_G") (class "Default")
      (node (ref "C27") (pin "2") (pinfunction "2_2") (pintype "passive"))
      (node (ref "R27") (pin "2") (pinfunction "2_2") (pintype "passive"))
      (node (ref "SW_G") (pin "3") (pinfunction "3_3") (pintype "passive"))
      (node (ref "SW_G") (pin "4") (pinfunction "4_4") (pintype "passive"))
    )
    (net (code "21") (name "/KEY_H") (class "Default")
      (node (ref "C32") (pin "2") (pinfunction "2_2") (pintype "passive"))
      (node (ref "R32") (pin "2") (pinfunction "2_2") (pintype "passive"))
      (node (ref "SW_H") (pin "3") (pinfunction "3_3") (pintype "passive"))
      (node (ref "SW_H") (pin "4") (pinfunction "4_4") (pintype "passive"))
    )
    (net (code "22") (name "/KEY_I") (class "Default")
      (node (ref "C35") (pin "2") (pinfunction "2_2") (pintype "passive"))
      (node (ref "R35") (pin "2") (pinfunction "2_2") (pintype "passive"))
      (node (ref "SW_I") (pin "3") (pinfunction "3_3") (pintype "passive"))
      (node (ref "SW_I") (pin "4") (pinfunction "4_4") (pintype "passive"))
    )
    (net (code "23") (name "/KEY_J") (class "Default")
      (node (ref "C36") (pin "2") (pinfunction "2_2") (pintype "passive"))
      (node (ref "R36") (pin "2") (pinfunction "2_2") (pintype "passive"))
      (node (ref "SW_J") (pin "3") (pinfunction "3_3") (pintype "passive"))
      (node (ref "SW_J") (pin "4") (pinfunction "4_4") (pintype "passive"))
    )
    (net (code "24") (name "/KEY_K") (class "Default")
      (node (ref "C40") (pin "2") (pinfunction "2_2") (pintype "passive"))
      (node (ref "R40") (pin "2") (pinfunction "2_2") (pintype "passive"))
      (node (ref "SW_K") (pin "3") (pinfunction "3_3") (pintype "passive"))
      (node (ref "SW_K") (pin "4") (pinfunction "4_4") (pintype "passive"))
    )
    (net (code "25") (name "/KEY_L") (class "Default")
      (node (ref "C3") (pin "2") (pinfunction "2_2") (pintype "passive"))
      (node (ref "R3") (pin "2") (pinfunction "2_2") (pintype "passive"))
      (node (ref "SW_L") (pin "3") (pinfunction "3_3") (pintype "passive"))
      (node (ref "SW_L") (pin "4") (pinfunction "4_4") (pintype "passive"))
    )
    (net (code "26") (name "/KEY_M") (class "Default")
      (node (ref "C37") (pin "2") (pinfunction "2_2") (pintype "passive"))
      (node (ref "R37") (pin "2") (pinfunction "2_2") (pintype "passive"))
      (node (ref "SW_M") (pin "3") (pinfunction "3_3") (pintype "passive"))
      (node (ref "SW_M") (pin "4") (pinfunction "4_4") (pintype "passive"))
    )
    (net (code "27") (name "/KEY_N") (class "Default")
      (node (ref "C33") (pin "2") (pinfunction "2_2") (pintype "passive"))
      (node (ref "R33") (pin "2") (pinfunction "2_2") (pintype "passive"))
      (node (ref "SW_N") (pin "3") (pinfunction "3_3") (pintype "passive"))
      (node (ref "SW_N") (pin "4") (pinfunction "4_4") (pintype "passive"))
    )
    (net (code "28") (name "/KEY_O") (class "Default")
      (node (ref "C39") (pin "2") (pinfunction "2_2") (pintype "passive"))
      (node (ref "R39") (pin "2") (pinfunction "2_2") (pintype "passive"))
      (node (ref "SW_O") (pin "3") (pinfunction "3_3") (pintype "passive"))
      (node (ref "SW_O") (pin "4") (pinfunction "4_4") (pintype "passive"))
    )
    (net (code "29") (name "/KEY_P") (class "Default")
      (node (ref "C2") (pin "2") (pinfunction "2_2") (pintype "passive"))
      (node (ref "R2") (pin "2") (pinfunction "2_2") (pintype "passive"))
      (node (ref "SW_P") (pin "3") (pinfunction "3_3") (pintype "passive"))
      (node (ref "SW_P") (pin "4") (pinfunction "4_4") (pintype "passive"))
    )
    (net (code "30") (name "/KEY_Q") (class "Default")
      (node (ref "C1") (pin "2") (pinfunction "2_2") (pintype "passive"))
      (node (ref "R1") (pin "2") (pinfunction "2_2") (pintype "passive"))
      (node (ref "SW_Q") (pin "3") (pinfunction "3_3") (pintype "passive"))
      (node (ref "SW_Q") (pin "4") (pinfunction "4_4") (pintype "passive"))
    )
    (net (code "31") (name "/KEY_R") (class "Default")
      (node (ref "C16") (pin "2") (pinfunction "2_2") (pintype "passive"))
      (node (ref "R16") (pin "2") (pinfunction "2_2") (pintype "passive"))
      (node (ref "SW_R") (pin "3") (pinfunction "3_3") (pintype "passive"))
      (node (ref "SW_R") (pin "4") (pinfunction "4_4") (pintype "passive"))
    )
    (net (code "32") (name "/KEY_S") (class "Default")
      (node (ref "C12") (pin "2") (pinfunction "2_2") (pintype "passive"))
      (node (ref "R12") (pin "2") (pinfunction "2_2") (pintype "passive"))
      (node (ref "SW_S") (pin "3") (pinfunction "3_3") (pintype "passive"))
      (node (ref "SW_S") (pin "4") (pinfunction "4_4") (pintype "passive"))
    )
    (net (code "33") (name "/KEY_Select") (class "Default")
      (node (ref "C20") (pin "2") (pinfunction "2_2") (pintype "passive"))
      (node (ref "R20") (pin "2") (pinfunction "2_2") (pintype "passive"))
      (node (ref "SW_Select") (pin "3") (pinfunction "3_3") (pintype "passive"))
      (node (ref "SW_Select") (pin "4") (pinfunction "4_4") (pintype "passive"))
    )
    (net (code "34") (name "/KEY_Shift") (class "Default")
      (node (ref "C5") (pin "1") (pinfunction "1_1") (pintype "passive"))
      (node (ref "R5") (pin "1") (pinfunction "1_1") (pintype "passive"))
      (node (ref "SW_Shift") (pin "3") (pinfunction "3_3") (pintype "passive"))
      (node (ref "SW_Shift") (pin "4") (pinfunction "4_4") (pintype "passive"))
    )
    (net (code "35") (name "/KEY_Space") (class "Default")
      (node (ref "C30") (pin "1") (pinfunction "1_1") (pintype "passive"))
      (node (ref "R30") (pin "2") (pinfunction "2_2") (pintype "passive"))
      (node (ref "SW_Space1") (pin "3") (pinfunction "3_3") (pintype "passive"))
      (node (ref "SW_Space1") (pin "4") (pinfunction "4_4") (pintype "passive"))
      (node (ref "SW_Space2") (pin "3") (pinfunction "3_3") (pintype "passive"))
      (node (ref "SW_Space2") (pin "4") (pinfunction "4_4") (pintype "passive"))
    )
    (net (code "36") (name "/KEY_T") (class "Default")
      (node (ref "C21") (pin "2") (pinfunction "2_2") (pintype "passive"))
      (node (ref "R21") (pin "2") (pinfunction "2_2") (pintype "passive"))
      (node (ref "SW_T") (pin "3") (pinfunction "3_3") (pintype "passive"))
      (node (ref "SW_T") (pin "4") (pinfunction "4_4") (pintype "passive"))
    )
    (net (code "37") (name "/KEY_U") (class "Default")
      (node (ref "C31") (pin "2") (pinfunction "2_2") (pintype "passive"))
      (node (ref "R31") (pin "2") (pinfunction "2_2") (pintype "passive"))
      (node (ref "SW_U") (pin "3") (pinfunction "3_3") (pintype "passive"))
      (node (ref "SW_U") (pin "4") (pinfunction "4_4") (pintype "passive"))
    )
    (net (code "38") (name "/KEY_Up") (class "Default")
      (node (ref "C10") (pin "2") (pinfunction "2_2") (pintype "passive"))
      (node (ref "R10") (pin "2") (pinfunction "2_2") (pintype "passive"))
      (node (ref "SW_Up") (pin "3") (pinfunction "3_3") (pintype "passive"))
      (node (ref "SW_Up") (pin "4") (pinfunction "4_4") (pintype "passive"))
    )
    (net (code "39") (name "/KEY_V") (class "Default")
      (node (ref "C23") (pin "2") (pinfunction "2_2") (pintype "passive"))
      (node (ref "R23") (pin "2") (pinfunction "2_2") (pintype "passive"))
      (node (ref "SW_V") (pin "3") (pinfunction "3_3") (pintype "passive"))
      (node (ref "SW_V") (pin "4") (pinfunction "4_4") (pintype "passive"))
    )
    (net (code "40") (name "/KEY_W") (class "Default")
      (node (ref "C6") (pin "2") (pinfunction "2_2") (pintype "passive"))
      (node (ref "R6") (pin "2") (pinfunction "2_2") (pintype "passive"))
      (node (ref "SW_W") (pin "3") (pinfunction "3_3") (pintype "passive"))
      (node (ref "SW_W") (pin "4") (pinfunction "4_4") (pintype "passive"))
    )
    (net (code "41") (name "/KEY_X") (class "Default")
      (node (ref "C13") (pin "2") (pinfunction "2_2") (pintype "passive"))
      (node (ref "R13") (pin "2") (pinfunction "2_2") (pintype "passive"))
      (node (ref "SW_X") (pin "3") (pinfunction "3_3") (pintype "passive"))
      (node (ref "SW_X") (pin "4") (pinfunction "4_4") (pintype "passive"))
    )
    (net (code "42") (name "/KEY_Y") (class "Default")
      (node (ref "C26") (pin "2") (pinfunction "2_2") (pintype "passive"))
      (node (ref "R26") (pin "2") (pinfunction "2_2") (pintype "passive"))
      (node (ref "SW_Y") (pin "3") (pinfunction "3_3") (pintype "passive"))
      (node (ref "SW_Y") (pin "4") (pinfunction "4_4") (pintype "passive"))
    )
    (net (code "43") (name "/KEY_Z") (class "Default")
      (node (ref "C8") (pin "2") (pinfunction "2_2") (pintype "passive"))
      (node (ref "R8") (pin "2") (pinfunction "2_2") (pintype "passive"))
      (node (ref "SW_Z") (pin "3") (pinfunction "3_3") (pintype "passive"))
      (node (ref "SW_Z") (pin "4") (pinfunction "4_4") (pintype "passive"))
    )
    (net (code "44") (name "GND") (class "Default")
      (node (ref "C1") (pin "1") (pinfunction "1_1") (pintype "passive"))
      (node (ref "C10") (pin "1") (pinfunction "1_1") (pintype "passive"))
      (node (ref "C11") (pin "1") (pinfunction "1_1") (pintype "passive"))
      (node (ref "C12") (pin "1") (pinfunction "1_1") (pintype "passive"))
      (node (ref "C13") (pin "1") (pinfunction "1_1") (pintype "passive"))
      (node (ref "C14") (pin "1") (pinfunction "1_1") (pintype "passive"))
      (node (ref "C15") (pin "1") (pinfunction "1_1") (pintype "passive"))
      (node (ref "C16") (pin "1") (pinfunction "1_1") (pintype "passive"))
      (node (ref "C17") (pin "1") (pinfunction "1_1") (pintype "passive"))
      (node (ref "C18") (pin "1") (pinfunction "1_1") (pintype "passive"))
      (node (ref "C19") (pin "1") (pinfunction "1_1") (pintype "passive"))
      (node (ref "C2") (pin "1") (pinfunction "1_1") (pintype "passive"))
      (node (ref "C20") (pin "1") (pinfunction "1_1") (pintype "passive"))
      (node (ref "C21") (pin "1") (pinfunction "1_1") (pintype "passive"))
      (node (ref "C22") (pin "1") (pinfunction "1_1") (pintype "passive"))
      (node (ref "C23") (pin "1") (pinfunction "1_1") (pintype "passive"))
      (node (ref "C24") (pin "1") (pinfunction "1_1") (pintype "passive"))
      (node (ref "C25") (pin "1") (pinfunction "1_1") (pintype "passive"))
      (node (ref "C26") (pin "1") (pinfunction "1_1") (pintype "passive"))
      (node (ref "C27") (pin "1") (pinfunction "1_1") (pintype "passive"))
      (node (ref "C28") (pin "1") (pinfunction "1_1") (pintype "passive"))
      (node (ref "C29") (pin "1") (pinfunction "1_1") (pintype "passive"))
      (node (ref "C3") (pin "1") (pinfunction "1_1") (pintype "passive"))
      (node (ref "C30") (pin "2") (pinfunction "2_2") (pintype "passive"))
      (node (ref "C31") (pin "1") (pinfunction "1_1") (pintype "passive"))
      (node (ref "C32") (pin "1") (pinfunction "1_1") (pintype "passive"))
      (node (ref "C33") (pin "1") (pinfunction "1_1") (pintype "passive"))
      (node (ref "C34") (pin "1") (pinfunction "1_1") (pintype "passive"))
      (node (ref "C35") (pin "1") (pinfunction "1_1") (pintype "passive"))
      (node (ref "C36") (pin "1") (pinfunction "1_1") (pintype "passive"))
      (node (ref "C37") (pin "1") (pinfunction "1_1") (pintype "passive"))
      (node (ref "C38") (pin "1") (pinfunction "1_1") (pintype "passive"))
      (node (ref "C39") (pin "1") (pinfunction "1_1") (pintype "passive"))
      (node (ref "C4") (pin "1") (pinfunction "1_1") (pintype "passive"))
      (node (ref "C40") (pin "1") (pinfunction "1_1") (pintype "passive"))
      (node (ref "C41") (pin "1") (pinfunction "1_1") (pintype "passive"))
      (node (ref "C42") (pin "1") (pinfunction "1_1") (pintype "passive"))
      (node (ref "C5") (pin "2") (pinfunction "2_2") (pintype "passive"))
      (node (ref "C6") (pin "1") (pinfunction "1_1") (pintype "passive"))
      (node (ref "C7") (pin "1") (pinfunction "1_1") (pintype "passive"))
      (node (ref "C8") (pin "1") (pinfunction "1_1") (pintype "passive"))
      (node (ref "C9") (pin "1") (pinfunction "1_1") (pintype "passive"))
      (node (ref "SW_0") (pin "1") (pinfunction "1_1") (pintype "passive"))
      (node (ref "SW_0") (pin "2") (pinfunction "2_2") (pintype "passive"))
      (node (ref "SW_1") (pin "1") (pinfunction "1_1") (pintype "passive"))
      (node (ref "SW_1") (pin "2") (pinfunction "2_2") (pintype "passive"))
      (node (ref "SW_2") (pin "1") (pinfunction "1_1") (pintype "passive"))
      (node (ref "SW_2") (pin "2") (pinfunction "2_2") (pintype "passive"))
      (node (ref "SW_3") (pin "1") (pinfunction "1_1") (pintype "passive"))
      (node (ref "SW_3") (pin "2") (pinfunction "2_2") (pintype "passive"))
      (node (ref "SW_4") (pin "1") (pinfunction "1_1") (pintype "passive"))
      (node (ref "SW_4") (pin "2") (pinfunction "2_2") (pintype "passive"))
      (node (ref "SW_5") (pin "1") (pinfunction "1_1") (pintype "passive"))
      (node (ref "SW_5") (pin "2") (pinfunction "2_2") (pintype "passive"))
      (node (ref "SW_6") (pin "1") (pinfunction "1_1") (pintype "passive"))
      (node (ref "SW_6") (pin "2") (pinfunction "2_2") (pintype "passive"))
      (node (ref "SW_7") (pin "1") (pinfunction "1_1") (pintype "passive"))
      (node (ref "SW_7") (pin "2") (pinfunction "2_2") (pintype "passive"))
      (node (ref "SW_8") (pin "1") (pinfunction "1_1") (pintype "passive"))
      (node (ref "SW_8") (pin "2") (pinfunction "2_2") (pintype "passive"))
      (node (ref "SW_9") (pin "1") (pinfunction "1_1") (pintype "passive"))
      (node (ref "SW_9") (pin "2") (pinfunction "2_2") (pintype "passive"))
      (node (ref "SW_A") (pin "1") (pinfunction "1_1") (pintype "passive"))
      (node (ref "SW_A") (pin "2") (pinfunction "2_2") (pintype "passive"))
      (node (ref "SW_B") (pin "1") (pinfunction "1_1") (pintype "passive"))
      (node (ref "SW_B") (pin "2") (pinfunction "2_2") (pintype "passive"))
      (node (ref "SW_Back") (pin "1") (pinfunction "1_1") (pintype "passive"))
      (node (ref "SW_Back") (pin "2") (pinfunction "2_2") (pintype "passive"))
      (node (ref "SW_C") (pin "1") (pinfunction "1_1") (pintype "passive"))
      (node (ref "SW_C") (pin "2") (pinfunction "2_2") (pintype "passive"))
      (node (ref "SW_D") (pin "1") (pinfunction "1_1") (pintype "passive"))
      (node (ref "SW_D") (pin "2") (pinfunction "2_2") (pintype "passive"))
      (node (ref "SW_Down") (pin "1") (pinfunction "1_1") (pintype "passive"))
      (node (ref "SW_Down") (pin "2") (pinfunction "2_2") (pintype "passive"))
      (node (ref "SW_E") (pin "1") (pinfunction "1_1") (pintype "passive"))
      (node (ref "SW_E") (pin "2") (pinfunction "2_2") (pintype "passive"))
      (node (ref "SW_F") (pin "1") (pinfunction "1_1") (pintype "passive"))
      (node (ref "SW_F") (pin "2") (pinfunction "2_2") (pintype "passive"))
      (node (ref "SW_G") (pin "1") (pinfunction "1_1") (pintype "passive"))
      (node (ref "SW_G") (pin "2") (pinfunction "2_2") (pintype "passive"))
      (node (ref "SW_H") (pin "1") (pinfunction "1_1") (pintype "passive"))
      (node (ref "SW_H") (pin "2") (pinfunction "2_2") (pintype "passive"))
      (node (ref "SW_I") (pin "1") (pinfunction "1_1") (pintype "passive"))
      (node (ref "SW_I") (pin "2") (pinfunction "2_2") (pintype "passive"))
      (node (ref "SW_J") (pin "1") (pinfunction "1_1") (pintype "passive"))
      (node (ref "SW_J") (pin "2") (pinfunction "2_2") (pintype "passive"))
      (node (ref "SW_K") (pin "1") (pinfunction "1_1") (pintype "passive"))
      (node (ref "SW_K") (pin "2") (pinfunction "2_2") (pintype "passive"))
      (node (ref "SW_L") (pin "1") (pinfunction "1_1") (pintype "passive"))
      (node (ref "SW_L") (pin "2") (pinfunction "2_2") (pintype "passive"))
      (node (ref "SW_M") (pin "1") (pinfunction "1_1") (pintype "passive"))
      (node (ref "SW_M") (pin "2") (pinfunction "2_2") (pintype "passive"))
      (node (ref "SW_N") (pin "1") (pinfunction "1_1") (pintype "passive"))
      (node (ref "SW_N") (pin "2") (pinfunction "2_2") (pintype "passive"))
      (node (ref "SW_O") (pin "1") (pinfunction "1_1") (pintype "passive"))
      (node (ref "SW_O") (pin "2") (pinfunction "2_2") (pintype "passive"))
      (node (ref "SW_P") (pin "1") (pinfunction "1_1") (pintype "passive"))
      (node (ref "SW_P") (pin "2") (pinfunction "2_2") (pintype "passive"))
      (node (ref "SW_Q") (pin "1") (pinfunction "1_1") (pintype "passive"))
      (node (ref "SW_Q") (pin "2") (pinfunction "2_2") (pintype "passive"))
      (node (ref "SW_R") (pin "1") (pinfunction "1_1") (pintype "passive"))
      (node (ref "SW_R") (pin "2") (pinfunction "2_2") (pintype "passive"))
      (node (ref "SW_S") (pin "1") (pinfunction "1_1") (pintype "passive"))
      (node (ref "SW_S") (pin "2") (pinfunction "2_2") (pintype "passive"))
      (node (ref "SW_Select") (pin "1") (pinfunction "1_1") (pintype "passive"))
      (node (ref "SW_Select") (pin "2") (pinfunction "2_2") (pintype "passive"))
      (node (ref "SW_Shift") (pin "1") (pinfunction "1_1") (pintype "passive"))
      (node (ref "SW_Shift") (pin "2") (pinfunction "2_2") (pintype "passive"))
      (node (ref "SW_Space1") (pin "1") (pinfunction "1_1") (pintype "passive"))
      (node (ref "SW_Space1") (pin "2") (pinfunction "2_2") (pintype "passive"))
      (node (ref "SW_Space2") (pin "1") (pinfunction "1_1") (pintype "passive"))
      (node (ref "SW_Space2") (pin "2") (pinfunction "2_2") (pintype "passive"))
      (node (ref "SW_T") (pin "1") (pinfunction "1_1") (pintype "passive"))
      (node (ref "SW_T") (pin "2") (pinfunction "2_2") (pintype "passive"))
      (node (ref "SW_U") (pin "1") (pinfunction "1_1") (pintype "passive"))
      (node (ref "SW_U") (pin "2") (pinfunction "2_2") (pintype "passive"))
      (node (ref "SW_Up") (pin "1") (pinfunction "1_1") (pintype "passive"))
      (node (ref "SW_Up") (pin "2") (pinfunction "2_2") (pintype "passive"))
      (node (ref "SW_V") (pin "1") (pinfunction "1_1") (pintype "passive"))
      (node (ref "SW_V") (pin "2") (pinfunction "2_2") (pintype "passive"))
      (node (ref "SW_W") (pin "1") (pinfunction "1_1") (pintype "passive"))
      (node (ref "SW_W") (pin "2") (pinfunction "2_2") (pintype "passive"))
      (node (ref "SW_X") (pin "1") (pinfunction "1_1") (pintype "passive"))
      (node (ref "SW_X") (pin "2") (pinfunction "2_2") (pintype "passive"))
      (node (ref "SW_Y") (pin "1") (pinfunction "1_1") (pintype "passive"))
      (node (ref "SW_Y") (pin "2") (pinfunction "2_2") (pintype "passive"))
      (node (ref "SW_Z") (pin "1") (pinfunction "1_1") (pintype "passive"))
      (node (ref "SW_Z") (pin "2") (pinfunction "2_2") (pintype "passive"))
    )
  )
)
